# drv.net
KiCad netlist of a schematic drawn in Altium Designer
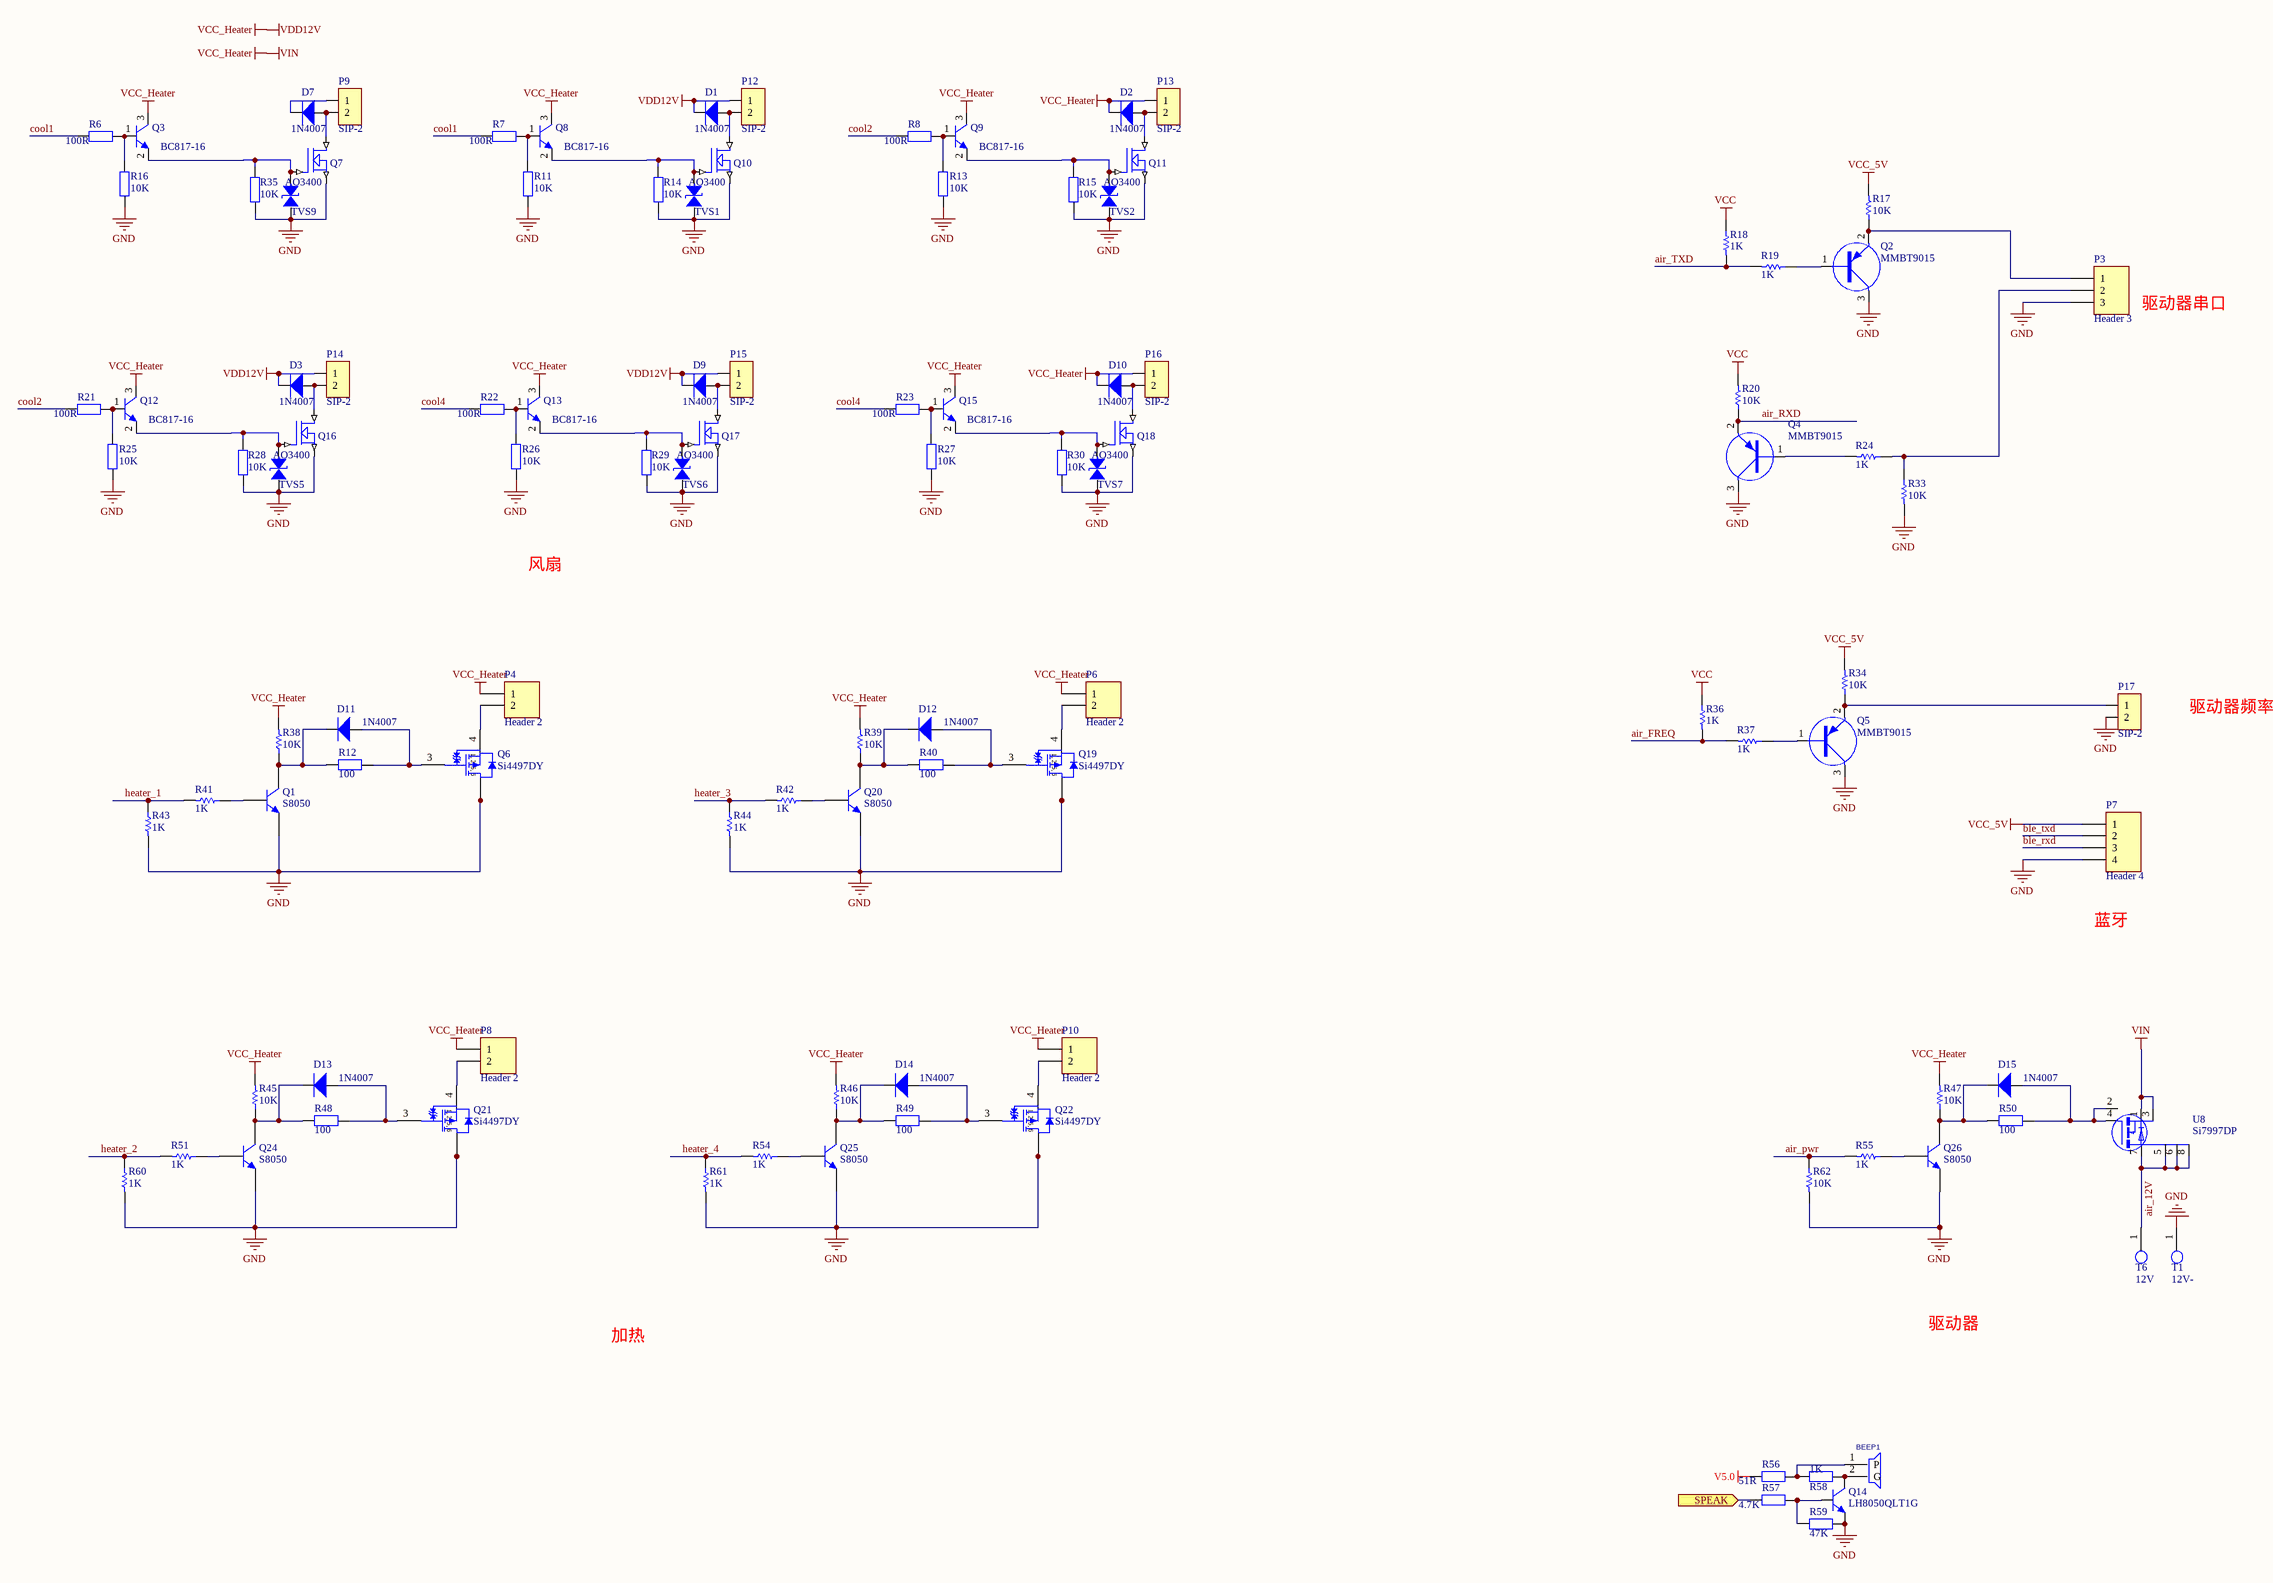
[diagram p0: drv.SchDoc]

(export (version "E")
  (design (tool "Eeschema 10.0.6"))
  (components
    (comp (ref "BEEP1")
      (value "BEEP-9.5X5.5")
      (footprint "BEEP-9.5X5.5")
      (libsource (lib "MINI-V3") (part "BEEP-9.5X5.5"))
    )
    (comp (ref "D1")
      (value "1N4007")
      (footprint "DO-214-AC")
      (description "贴片二极管")
      (libsource (lib "XiaoyI") (part "DIODE2"))
    )
    (comp (ref "D2")
      (value "1N4007")
      (footprint "DO-214-AC")
      (description "贴片二极管")
      (libsource (lib "XiaoyI") (part "DIODE2"))
    )
    (comp (ref "D3")
      (value "1N4007")
      (footprint "DO-214-AC")
      (description "贴片二极管")
      (libsource (lib "XiaoyI") (part "DIODE2"))
    )
    (comp (ref "D7")
      (value "1N4007")
      (footprint "DO-214-AC")
      (description "贴片二极管")
      (libsource (lib "XiaoyI") (part "DIODE2"))
    )
    (comp (ref "D9")
      (value "1N4007")
      (footprint "DO-214-AC")
      (description "贴片二极管")
      (libsource (lib "XiaoyI") (part "DIODE2"))
    )
    (comp (ref "D10")
      (value "1N4007")
      (footprint "DO-214-AC")
      (description "贴片二极管")
      (libsource (lib "XiaoyI") (part "DIODE2"))
    )
    (comp (ref "D11")
      (value "1N4007")
      (footprint "DO-214-AC")
      (description "贴片二极管")
      (libsource (lib "XiaoyI") (part "DIODE2"))
    )
    (comp (ref "D12")
      (value "1N4007")
      (footprint "DO-214-AC")
      (description "贴片二极管")
      (libsource (lib "XiaoyI") (part "DIODE2"))
    )
    (comp (ref "D13")
      (value "1N4007")
      (footprint "DO-214-AC")
      (description "贴片二极管")
      (libsource (lib "XiaoyI") (part "DIODE2"))
    )
    (comp (ref "D14")
      (value "1N4007")
      (footprint "DO-214-AC")
      (description "贴片二极管")
      (libsource (lib "XiaoyI") (part "DIODE2"))
    )
    (comp (ref "D15")
      (value "1N4007")
      (footprint "DO-214-AC")
      (description "贴片二极管")
      (libsource (lib "XiaoyI") (part "DIODE2"))
    )
    (comp (ref "P3")
      (value "Header 3")
      (footprint "HDR1X3")
      (description "Header, 3-Pin")
      (fields (field (name "PUBLISHER") "Altium Limited"))
      (libsource (lib "Miscellaneous Connectors") (part "Header 3"))
    )
    (comp (ref "P4")
      (value "Header 2")
      (footprint "HDR1X2")
      (description "Header, 2-Pin")
      (fields (field (name "PUBLISHER") "Altium Limited"))
      (libsource (lib "Miscellaneous Connectors") (part "Header 2"))
    )
    (comp (ref "P6")
      (value "Header 2")
      (footprint "HDR1X2")
      (description "Header, 2-Pin")
      (fields (field (name "PUBLISHER") "Altium Limited"))
      (libsource (lib "Miscellaneous Connectors") (part "Header 2"))
    )
    (comp (ref "P7")
      (value "Header 4")
      (footprint "HDR1X4")
      (description "Header, 4-Pin")
      (fields (field (name "PUBLISHER") "Altium Limited"))
      (libsource (lib "Miscellaneous Connectors") (part "Header 4"))
    )
    (comp (ref "P8")
      (value "Header 2")
      (footprint "HDR1X2")
      (description "Header, 2-Pin")
      (fields (field (name "PUBLISHER") "Altium Limited"))
      (libsource (lib "Miscellaneous Connectors") (part "Header 2"))
    )
    (comp (ref "P9")
      (value "SIP-2")
      (footprint "SIP-2A")
      (description "XH2.54 2P 立贴")
      (libsource (lib "XiaoyI") (part "SIP-2"))
    )
    (comp (ref "P10")
      (value "Header 2")
      (footprint "HDR1X2")
      (description "Header, 2-Pin")
      (fields (field (name "PUBLISHER") "Altium Limited"))
      (libsource (lib "Miscellaneous Connectors") (part "Header 2"))
    )
    (comp (ref "P12")
      (value "SIP-2")
      (footprint "SIP-2A")
      (description "XH2.54 2P 立贴")
      (libsource (lib "XiaoyI") (part "SIP-2"))
    )
    (comp (ref "P13")
      (value "SIP-2")
      (footprint "SIP-2A")
      (description "XH2.54 2P 立贴")
      (libsource (lib "XiaoyI") (part "SIP-2"))
    )
    (comp (ref "P14")
      (value "SIP-2")
      (footprint "SIP-2A")
      (description "XH2.54 2P 立贴")
      (libsource (lib "XiaoyI") (part "SIP-2"))
    )
    (comp (ref "P15")
      (value "SIP-2")
      (footprint "SIP-2A")
      (description "XH2.54 2P 立贴")
      (libsource (lib "XiaoyI") (part "SIP-2"))
    )
    (comp (ref "P16")
      (value "SIP-2")
      (footprint "SIP-2A")
      (description "XH2.54 2P 立贴")
      (libsource (lib "XiaoyI") (part "SIP-2"))
    )
    (comp (ref "P17")
      (value "SIP-2")
      (footprint "SIP-2A")
      (description "XH2.54 2P 立贴")
      (libsource (lib "XiaoyI") (part "SIP-2"))
    )
    (comp (ref "Q1")
      (value "S8050")
      (footprint "SOT23-3")
      (description "NPN Bipolar Transistor")
      (fields (field (name "PUBLISHER") "Altium Limited"))
      (libsource (lib "Miscellaneous Devices") (part "NPN"))
    )
    (comp (ref "Q2") (value "MMBT9015") (footprint "SOT23-3") (libsource (lib "Schlib1") (part "PNP")))
    (comp (ref "Q3")
      (value "BC817-16")
      (footprint "SOT-23")
      (description "三极管")
      (libsource (lib "XiaoyI") (part "NPN-1"))
    )
    (comp (ref "Q4") (value "MMBT9015") (footprint "SOT23-3") (libsource (lib "Schlib1") (part "PNP")))
    (comp (ref "Q5") (value "MMBT9015") (footprint "SOT23-3") (libsource (lib "Schlib1") (part "PNP")))
    (comp (ref "Q6")
      (value "Si4497DY")
      (description "Automotive P-Channel MOSFET, 6.9 A, 40 V, -55 to 175 degC, 6-Pin TSOP, RoHS, Tape and Reel")
      (fields (field (name "MANUFACTURER") "International Rectifier"))
      (libsource (lib "Bogen") (part "SQ3419AEEV-T1_GE3"))
    )
    (comp (ref "Q7")
      (value "AO3400")
      (footprint "SOT-23")
      (description "MOSFET N")
      (libsource (lib "XiaoyI") (part "MOSFET N"))
    )
    (comp (ref "Q8")
      (value "BC817-16")
      (footprint "SOT-23")
      (description "三极管")
      (libsource (lib "XiaoyI") (part "NPN-1"))
    )
    (comp (ref "Q9")
      (value "BC817-16")
      (footprint "SOT-23")
      (description "三极管")
      (libsource (lib "XiaoyI") (part "NPN-1"))
    )
    (comp (ref "Q10")
      (value "AO3400")
      (footprint "SOT-23")
      (description "MOSFET N")
      (libsource (lib "XiaoyI") (part "MOSFET N"))
    )
    (comp (ref "Q11")
      (value "AO3400")
      (footprint "SOT-23")
      (description "MOSFET N")
      (libsource (lib "XiaoyI") (part "MOSFET N"))
    )
    (comp (ref "Q12")
      (value "BC817-16")
      (footprint "SOT-23")
      (description "三极管")
      (libsource (lib "XiaoyI") (part "NPN-1"))
    )
    (comp (ref "Q13")
      (value "BC817-16")
      (footprint "SOT-23")
      (description "三极管")
      (libsource (lib "XiaoyI") (part "NPN-1"))
    )
    (comp (ref "Q14")
      (value "LH8050QLT1G")
      (footprint "SOT-23")
      (description "NPN")
      (libsource (lib "") (part "NPN-1_1"))
    )
    (comp (ref "Q15")
      (value "BC817-16")
      (footprint "SOT-23")
      (description "三极管")
      (libsource (lib "XiaoyI") (part "NPN-1"))
    )
    (comp (ref "Q16")
      (value "AO3400")
      (footprint "SOT-23")
      (description "MOSFET N")
      (libsource (lib "XiaoyI") (part "MOSFET N"))
    )
    (comp (ref "Q17")
      (value "AO3400")
      (footprint "SOT-23")
      (description "MOSFET N")
      (libsource (lib "XiaoyI") (part "MOSFET N"))
    )
    (comp (ref "Q18")
      (value "AO3400")
      (footprint "SOT-23")
      (description "MOSFET N")
      (libsource (lib "XiaoyI") (part "MOSFET N"))
    )
    (comp (ref "Q19")
      (value "Si4497DY")
      (description "Automotive P-Channel MOSFET, 6.9 A, 40 V, -55 to 175 degC, 6-Pin TSOP, RoHS, Tape and Reel")
      (fields (field (name "MANUFACTURER") "International Rectifier"))
      (libsource (lib "Bogen") (part "SQ3419AEEV-T1_GE3"))
    )
    (comp (ref "Q20")
      (value "S8050")
      (footprint "SOT23-3")
      (description "NPN Bipolar Transistor")
      (fields (field (name "PUBLISHER") "Altium Limited"))
      (libsource (lib "Miscellaneous Devices") (part "NPN"))
    )
    (comp (ref "Q21")
      (value "Si4497DY")
      (description "Automotive P-Channel MOSFET, 6.9 A, 40 V, -55 to 175 degC, 6-Pin TSOP, RoHS, Tape and Reel")
      (fields (field (name "MANUFACTURER") "International Rectifier"))
      (libsource (lib "Bogen") (part "SQ3419AEEV-T1_GE3"))
    )
    (comp (ref "Q22")
      (value "Si4497DY")
      (description "Automotive P-Channel MOSFET, 6.9 A, 40 V, -55 to 175 degC, 6-Pin TSOP, RoHS, Tape and Reel")
      (fields (field (name "MANUFACTURER") "International Rectifier"))
      (libsource (lib "Bogen") (part "SQ3419AEEV-T1_GE3"))
    )
    (comp (ref "Q24")
      (value "S8050")
      (footprint "SOT23-3")
      (description "NPN Bipolar Transistor")
      (fields (field (name "PUBLISHER") "Altium Limited"))
      (libsource (lib "Miscellaneous Devices") (part "NPN"))
    )
    (comp (ref "Q25")
      (value "S8050")
      (footprint "SOT23-3")
      (description "NPN Bipolar Transistor")
      (fields (field (name "PUBLISHER") "Altium Limited"))
      (libsource (lib "Miscellaneous Devices") (part "NPN"))
    )
    (comp (ref "Q26")
      (value "S8050")
      (footprint "SOT23-3")
      (description "NPN Bipolar Transistor")
      (fields (field (name "PUBLISHER") "Altium Limited"))
      (libsource (lib "Miscellaneous Devices") (part "NPN"))
    )
    (comp (ref "R6")
      (value "100R")
      (footprint "0603R")
      (description "贴片电阻 5%")
      (libsource (lib "") (part "RES-SOP_1"))
    )
    (comp (ref "R7")
      (value "100R")
      (footprint "0603R")
      (description "贴片电阻 5%")
      (libsource (lib "") (part "RES-SOP_1"))
    )
    (comp (ref "R8")
      (value "100R")
      (footprint "0603R")
      (description "贴片电阻 5%")
      (libsource (lib "") (part "RES-SOP_1"))
    )
    (comp (ref "R11")
      (value "10K")
      (footprint "0603R")
      (description "贴片电阻 5%")
      (libsource (lib "XiaoyI") (part "RES-SOP"))
    )
    (comp (ref "R12")
      (value "100")
      (footprint "0603R")
      (description "贴片电阻 5%")
      (libsource (lib "") (part "RES-SOP_2"))
    )
    (comp (ref "R13")
      (value "10K")
      (footprint "0603R")
      (description "贴片电阻 5%")
      (libsource (lib "XiaoyI") (part "RES-SOP"))
    )
    (comp (ref "R14")
      (value "10K")
      (footprint "0603R")
      (description "贴片电阻 5%")
      (libsource (lib "") (part "RES-SOP_3"))
    )
    (comp (ref "R15")
      (value "10K")
      (footprint "0603R")
      (description "贴片电阻 5%")
      (libsource (lib "") (part "RES-SOP_3"))
    )
    (comp (ref "R16")
      (value "10K")
      (footprint "0603R")
      (description "贴片电阻 5%")
      (libsource (lib "XiaoyI") (part "RES-SOP"))
    )
    (comp (ref "R17")
      (value "10K")
      (footprint "0603R")
      (description "Resistor")
      (fields (field (name "PUBLISHER") "Altium Limited"))
      (libsource (lib "Miscellaneous Devices") (part "Res1"))
    )
    (comp (ref "R18")
      (value "1K")
      (footprint "0603R")
      (description "Resistor")
      (fields (field (name "PUBLISHER") "Altium Limited"))
      (libsource (lib "Miscellaneous Devices") (part "Res1"))
    )
    (comp (ref "R19")
      (value "1K")
      (footprint "0603R")
      (description "Resistor")
      (fields (field (name "PUBLISHER") "Altium Limited"))
      (libsource (lib "Miscellaneous Devices") (part "Res1"))
    )
    (comp (ref "R20")
      (value "10K")
      (footprint "0603R")
      (description "Resistor")
      (fields (field (name "PUBLISHER") "Altium Limited"))
      (libsource (lib "Miscellaneous Devices") (part "Res1"))
    )
    (comp (ref "R21")
      (value "100R")
      (footprint "0603R")
      (description "贴片电阻 5%")
      (libsource (lib "") (part "RES-SOP_1"))
    )
    (comp (ref "R22")
      (value "100R")
      (footprint "0603R")
      (description "贴片电阻 5%")
      (libsource (lib "") (part "RES-SOP_1"))
    )
    (comp (ref "R23")
      (value "100R")
      (footprint "0603R")
      (description "贴片电阻 5%")
      (libsource (lib "") (part "RES-SOP_1"))
    )
    (comp (ref "R24")
      (value "1K")
      (footprint "0603R")
      (description "Resistor")
      (fields (field (name "PUBLISHER") "Altium Limited"))
      (libsource (lib "Miscellaneous Devices") (part "Res1"))
    )
    (comp (ref "R25")
      (value "10K")
      (footprint "0603R")
      (description "贴片电阻 5%")
      (libsource (lib "XiaoyI") (part "RES-SOP"))
    )
    (comp (ref "R26")
      (value "10K")
      (footprint "0603R")
      (description "贴片电阻 5%")
      (libsource (lib "XiaoyI") (part "RES-SOP"))
    )
    (comp (ref "R27")
      (value "10K")
      (footprint "0603R")
      (description "贴片电阻 5%")
      (libsource (lib "XiaoyI") (part "RES-SOP"))
    )
    (comp (ref "R28")
      (value "10K")
      (footprint "0603R")
      (description "贴片电阻 5%")
      (libsource (lib "") (part "RES-SOP_3"))
    )
    (comp (ref "R29")
      (value "10K")
      (footprint "0603R")
      (description "贴片电阻 5%")
      (libsource (lib "") (part "RES-SOP_3"))
    )
    (comp (ref "R30")
      (value "10K")
      (footprint "0603R")
      (description "贴片电阻 5%")
      (libsource (lib "") (part "RES-SOP_3"))
    )
    (comp (ref "R33")
      (value "10K")
      (footprint "0603R")
      (description "Resistor")
      (fields (field (name "PUBLISHER") "Altium Limited"))
      (libsource (lib "Miscellaneous Devices") (part "Res1"))
    )
    (comp (ref "R34")
      (value "10K")
      (footprint "0603R")
      (description "Resistor")
      (fields (field (name "PUBLISHER") "Altium Limited"))
      (libsource (lib "Miscellaneous Devices") (part "Res1"))
    )
    (comp (ref "R35")
      (value "10K")
      (footprint "0603R")
      (description "贴片电阻 5%")
      (libsource (lib "") (part "RES-SOP_3"))
    )
    (comp (ref "R36")
      (value "1K")
      (footprint "0603R")
      (description "Resistor")
      (fields (field (name "PUBLISHER") "Altium Limited"))
      (libsource (lib "Miscellaneous Devices") (part "Res1"))
    )
    (comp (ref "R37")
      (value "1K")
      (footprint "0603R")
      (description "Resistor")
      (fields (field (name "PUBLISHER") "Altium Limited"))
      (libsource (lib "Miscellaneous Devices") (part "Res1"))
    )
    (comp (ref "R38")
      (value "10K")
      (footprint "0603R")
      (description "Resistor")
      (fields (field (name "PUBLISHER") "Altium Limited"))
      (libsource (lib "Miscellaneous Devices") (part "Res1"))
    )
    (comp (ref "R39")
      (value "10K")
      (footprint "0603R")
      (description "Resistor")
      (fields (field (name "PUBLISHER") "Altium Limited"))
      (libsource (lib "Miscellaneous Devices") (part "Res1"))
    )
    (comp (ref "R40")
      (value "100")
      (footprint "0603R")
      (description "贴片电阻 5%")
      (libsource (lib "") (part "RES-SOP_2"))
    )
    (comp (ref "R41")
      (value "1K")
      (footprint "0603R")
      (description "Resistor")
      (fields (field (name "PUBLISHER") "Altium Limited"))
      (libsource (lib "Miscellaneous Devices") (part "Res1"))
    )
    (comp (ref "R42")
      (value "1K")
      (footprint "0603R")
      (description "Resistor")
      (fields (field (name "PUBLISHER") "Altium Limited"))
      (libsource (lib "Miscellaneous Devices") (part "Res1"))
    )
    (comp (ref "R43")
      (value "1K")
      (footprint "0603R")
      (description "Resistor")
      (fields (field (name "PUBLISHER") "Altium Limited"))
      (libsource (lib "Miscellaneous Devices") (part "Res1"))
    )
    (comp (ref "R44")
      (value "1K")
      (footprint "0603R")
      (description "Resistor")
      (fields (field (name "PUBLISHER") "Altium Limited"))
      (libsource (lib "Miscellaneous Devices") (part "Res1"))
    )
    (comp (ref "R45")
      (value "10K")
      (footprint "0603R")
      (description "Resistor")
      (fields (field (name "PUBLISHER") "Altium Limited"))
      (libsource (lib "Miscellaneous Devices") (part "Res1"))
    )
    (comp (ref "R46")
      (value "10K")
      (footprint "0603R")
      (description "Resistor")
      (fields (field (name "PUBLISHER") "Altium Limited"))
      (libsource (lib "Miscellaneous Devices") (part "Res1"))
    )
    (comp (ref "R47")
      (value "10K")
      (footprint "0603R")
      (description "Resistor")
      (fields (field (name "PUBLISHER") "Altium Limited"))
      (libsource (lib "Miscellaneous Devices") (part "Res1"))
    )
    (comp (ref "R48")
      (value "100")
      (footprint "0603R")
      (description "贴片电阻 5%")
      (libsource (lib "") (part "RES-SOP_2"))
    )
    (comp (ref "R49")
      (value "100")
      (footprint "0603R")
      (description "贴片电阻 5%")
      (libsource (lib "") (part "RES-SOP_2"))
    )
    (comp (ref "R50")
      (value "100")
      (footprint "0603R")
      (description "贴片电阻 5%")
      (libsource (lib "") (part "RES-SOP_2"))
    )
    (comp (ref "R51")
      (value "1K")
      (footprint "0603R")
      (description "Resistor")
      (fields (field (name "PUBLISHER") "Altium Limited"))
      (libsource (lib "Miscellaneous Devices") (part "Res1"))
    )
    (comp (ref "R54")
      (value "1K")
      (footprint "0603R")
      (description "Resistor")
      (fields (field (name "PUBLISHER") "Altium Limited"))
      (libsource (lib "Miscellaneous Devices") (part "Res1"))
    )
    (comp (ref "R55")
      (value "1K")
      (footprint "0603R")
      (description "Resistor")
      (fields (field (name "PUBLISHER") "Altium Limited"))
      (libsource (lib "Miscellaneous Devices") (part "Res1"))
    )
    (comp (ref "R56")
      (value "51R")
      (footprint "0603R")
      (description "贴片电阻 5%")
      (libsource (lib "ABB") (part "RES0"))
    )
    (comp (ref "R57")
      (value "4.7K")
      (footprint "0603R")
      (description "贴片电阻 5%")
      (libsource (lib "") (part "RES0_1"))
    )
    (comp (ref "R58")
      (value "1K")
      (footprint "0603R")
      (description "贴片电阻 5%")
      (libsource (lib "ABB") (part "RES0"))
    )
    (comp (ref "R59")
      (value "47K")
      (footprint "0603R")
      (description "贴片电阻 5%")
      (libsource (lib "") (part "RES0_1"))
    )
    (comp (ref "R60")
      (value "1K")
      (footprint "0603R")
      (description "Resistor")
      (fields (field (name "PUBLISHER") "Altium Limited"))
      (libsource (lib "Miscellaneous Devices") (part "Res1"))
    )
    (comp (ref "R61")
      (value "1K")
      (footprint "0603R")
      (description "Resistor")
      (fields (field (name "PUBLISHER") "Altium Limited"))
      (libsource (lib "Miscellaneous Devices") (part "Res1"))
    )
    (comp (ref "R62")
      (value "10K")
      (footprint "0603R")
      (description "Resistor")
      (fields (field (name "PUBLISHER") "Altium Limited"))
      (libsource (lib "Miscellaneous Devices") (part "Res1"))
    )
    (comp (ref "T1") (value "12V-") (footprint "FIX-4.5") (libsource (lib "Schlib_20110825") (part "TP")))
    (comp (ref "T6") (value "12V") (footprint "FIX-4.5") (libsource (lib "Schlib_20110825") (part "TP")))
    (comp (ref "TVS1")
      (value "ESD5Z5.0CT1G")
      (footprint "SOD-523")
      (description "TVS")
      (libsource (lib "XiaoyI") (part "TVS-1"))
    )
    (comp (ref "TVS2")
      (value "ESD5Z5.0CT1G")
      (footprint "SOD-523")
      (description "TVS")
      (libsource (lib "XiaoyI") (part "TVS-1"))
    )
    (comp (ref "TVS5")
      (value "ESD5Z5.0CT1G")
      (footprint "SOD-523")
      (description "TVS")
      (libsource (lib "XiaoyI") (part "TVS-1"))
    )
    (comp (ref "TVS6")
      (value "ESD5Z5.0CT1G")
      (footprint "SOD-523")
      (description "TVS")
      (libsource (lib "XiaoyI") (part "TVS-1"))
    )
    (comp (ref "TVS7")
      (value "ESD5Z5.0CT1G")
      (footprint "SOD-523")
      (description "TVS")
      (libsource (lib "XiaoyI") (part "TVS-1"))
    )
    (comp (ref "TVS9")
      (value "ESD5Z5.0CT1G")
      (footprint "SOD-523")
      (description "TVS")
      (libsource (lib "XiaoyI") (part "TVS-1"))
    )
    (comp (ref "U8")
      (value "Si7997DP")
      (footprint "SC-70(PowerPAK)")
      (description "Sia430DJ")
      (libsource (lib "Schlib_20110825") (part "Si7997DP"))
    )
  )
  (nets
    (net (code "1") (name "/SPEAK") (class "Default")
      (node (ref "R57") (pin "1") (pinfunction "1_1") (pintype "passive"))
    )
    (net (code "2") (name "/air_12V") (class "Default")
      (node (ref "T6") (pin "1") (pintype "passive"))
      (node (ref "U8") (pin "5") (pinfunction "D_5") (pintype "passive"))
      (node (ref "U8") (pin "6") (pinfunction "D_6") (pintype "passive"))
      (node (ref "U8") (pin "7") (pinfunction "D_7") (pintype "passive"))
      (node (ref "U8") (pin "8") (pinfunction "D_8") (pintype "passive"))
    )
    (net (code "3") (name "/air_FREQ") (class "Default")
      (node (ref "R36") (pin "2") (pinfunction "2_2") (pintype "passive"))
      (node (ref "R37") (pin "2") (pinfunction "2_2") (pintype "passive"))
    )
    (net (code "4") (name "/air_RXD") (class "Default")
      (node (ref "Q4") (pin "2") (pinfunction "E_2") (pintype "passive"))
      (node (ref "R20") (pin "1") (pinfunction "1_1") (pintype "passive"))
    )
    (net (code "5") (name "/air_TXD") (class "Default")
      (node (ref "R18") (pin "2") (pinfunction "2_2") (pintype "passive"))
      (node (ref "R19") (pin "2") (pinfunction "2_2") (pintype "passive"))
    )
    (net (code "6") (name "/air_pwr") (class "Default")
      (node (ref "R55") (pin "2") (pinfunction "2_2") (pintype "passive"))
      (node (ref "R62") (pin "1") (pinfunction "1_1") (pintype "passive"))
    )
    (net (code "7") (name "/ble_rxd") (class "Default")
      (node (ref "P7") (pin "3") (pinfunction "3_3") (pintype "passive"))
    )
    (net (code "8") (name "/ble_txd") (class "Default")
      (node (ref "P7") (pin "2") (pinfunction "2_2") (pintype "passive"))
    )
    (net (code "9") (name "/cool1") (class "Default")
      (node (ref "R6") (pin "2") (pinfunction "2_2") (pintype "passive"))
      (node (ref "R7") (pin "2") (pinfunction "2_2") (pintype "passive"))
    )
    (net (code "10") (name "/cool2") (class "Default")
      (node (ref "R21") (pin "2") (pinfunction "2_2") (pintype "passive"))
      (node (ref "R8") (pin "2") (pinfunction "2_2") (pintype "passive"))
    )
    (net (code "11") (name "/cool4") (class "Default")
      (node (ref "R22") (pin "2") (pinfunction "2_2") (pintype "passive"))
      (node (ref "R23") (pin "2") (pinfunction "2_2") (pintype "passive"))
    )
    (net (code "12") (name "/heater_1") (class "Default")
      (node (ref "R41") (pin "2") (pinfunction "2_2") (pintype "passive"))
      (node (ref "R43") (pin "1") (pinfunction "1_1") (pintype "passive"))
    )
    (net (code "13") (name "/heater_2") (class "Default")
      (node (ref "R51") (pin "2") (pinfunction "2_2") (pintype "passive"))
      (node (ref "R60") (pin "1") (pinfunction "1_1") (pintype "passive"))
    )
    (net (code "14") (name "/heater_3") (class "Default")
      (node (ref "R42") (pin "2") (pinfunction "2_2") (pintype "passive"))
      (node (ref "R44") (pin "1") (pinfunction "1_1") (pintype "passive"))
    )
    (net (code "15") (name "/heater_4") (class "Default")
      (node (ref "R54") (pin "2") (pinfunction "2_2") (pintype "passive"))
      (node (ref "R61") (pin "1") (pinfunction "1_1") (pintype "passive"))
    )
    (net (code "16") (name "GND") (class "Default")
      (node (ref "P17") (pin "2") (pinfunction "2_2") (pintype "passive"))
      (node (ref "P3") (pin "3") (pinfunction "3_3") (pintype "passive"))
      (node (ref "P7") (pin "4") (pinfunction "4_4") (pintype "passive"))
      (node (ref "Q1") (pin "2") (pinfunction "E_2") (pintype "passive"))
      (node (ref "Q10") (pin "2") (pinfunction "S_2") (pintype "output"))
      (node (ref "Q11") (pin "2") (pinfunction "S_2") (pintype "output"))
      (node (ref "Q14") (pin "2") (pinfunction "E_2") (pintype "passive"))
      (node (ref "Q16") (pin "2") (pinfunction "S_2") (pintype "output"))
      (node (ref "Q17") (pin "2") (pinfunction "S_2") (pintype "output"))
      (node (ref "Q18") (pin "2") (pinfunction "S_2") (pintype "output"))
      (node (ref "Q19") (pin "1") (pinfunction "D_1") (pintype "passive"))
      (node (ref "Q19") (pin "2") (pinfunction "D_2") (pintype "passive"))
      (node (ref "Q19") (pin "5") (pinfunction "D_5") (pintype "passive"))
      (node (ref "Q19") (pin "6") (pinfunction "D_6") (pintype "passive"))
      (node (ref "Q2") (pin "3") (pinfunction "C_3") (pintype "passive"))
      (node (ref "Q20") (pin "2") (pinfunction "E_2") (pintype "passive"))
      (node (ref "Q21") (pin "1") (pinfunction "D_1") (pintype "passive"))
      (node (ref "Q21") (pin "2") (pinfunction "D_2") (pintype "passive"))
      (node (ref "Q21") (pin "5") (pinfunction "D_5") (pintype "passive"))
      (node (ref "Q21") (pin "6") (pinfunction "D_6") (pintype "passive"))
      (node (ref "Q22") (pin "1") (pinfunction "D_1") (pintype "passive"))
      (node (ref "Q22") (pin "2") (pinfunction "D_2") (pintype "passive"))
      (node (ref "Q22") (pin "5") (pinfunction "D_5") (pintype "passive"))
      (node (ref "Q22") (pin "6") (pinfunction "D_6") (pintype "passive"))
      (node (ref "Q24") (pin "2") (pinfunction "E_2") (pintype "passive"))
      (node (ref "Q25") (pin "2") (pinfunction "E_2") (pintype "passive"))
      (node (ref "Q26") (pin "2") (pinfunction "E_2") (pintype "passive"))
      (node (ref "Q4") (pin "3") (pinfunction "C_3") (pintype "passive"))
      (node (ref "Q5") (pin "3") (pinfunction "C_3") (pintype "passive"))
      (node (ref "Q6") (pin "1") (pinfunction "D_1") (pintype "passive"))
      (node (ref "Q6") (pin "2") (pinfunction "D_2") (pintype "passive"))
      (node (ref "Q6") (pin "5") (pinfunction "D_5") (pintype "passive"))
      (node (ref "Q6") (pin "6") (pinfunction "D_6") (pintype "passive"))
      (node (ref "Q7") (pin "2") (pinfunction "S_2") (pintype "output"))
      (node (ref "R11") (pin "1") (pinfunction "1_1") (pintype "passive"))
      (node (ref "R13") (pin "1") (pinfunction "1_1") (pintype "passive"))
      (node (ref "R14") (pin "2") (pinfunction "2_2") (pintype "passive"))
      (node (ref "R15") (pin "2") (pinfunction "2_2") (pintype "passive"))
      (node (ref "R16") (pin "1") (pinfunction "1_1") (pintype "passive"))
      (node (ref "R25") (pin "1") (pinfunction "1_1") (pintype "passive"))
      (node (ref "R26") (pin "1") (pinfunction "1_1") (pintype "passive"))
      (node (ref "R27") (pin "1") (pinfunction "1_1") (pintype "passive"))
      (node (ref "R28") (pin "2") (pinfunction "2_2") (pintype "passive"))
      (node (ref "R29") (pin "2") (pinfunction "2_2") (pintype "passive"))
      (node (ref "R30") (pin "2") (pinfunction "2_2") (pintype "passive"))
      (node (ref "R33") (pin "2") (pinfunction "2_2") (pintype "passive"))
      (node (ref "R35") (pin "2") (pinfunction "2_2") (pintype "passive"))
      (node (ref "R43") (pin "2") (pinfunction "2_2") (pintype "passive"))
      (node (ref "R44") (pin "2") (pinfunction "2_2") (pintype "passive"))
      (node (ref "R59") (pin "2") (pinfunction "2_2") (pintype "passive"))
      (node (ref "R60") (pin "2") (pinfunction "2_2") (pintype "passive"))
      (node (ref "R61") (pin "2") (pinfunction "2_2") (pintype "passive"))
      (node (ref "R62") (pin "2") (pinfunction "2_2") (pintype "passive"))
      (node (ref "T1") (pin "1") (pintype "passive"))
      (node (ref "TVS1") (pin "1") (pinfunction "A_1") (pintype "passive"))
      (node (ref "TVS2") (pin "1") (pinfunction "A_1") (pintype "passive"))
      (node (ref "TVS5") (pin "1") (pinfunction "A_1") (pintype "passive"))
      (node (ref "TVS6") (pin "1") (pinfunction "A_1") (pintype "passive"))
      (node (ref "TVS7") (pin "1") (pinfunction "A_1") (pintype "passive"))
      (node (ref "TVS9") (pin "1") (pinfunction "A_1") (pintype "passive"))
    )
    (net (code "17") (name "Net-(BEEP1-G)") (class "Default")
      (node (ref "BEEP1") (pin "2") (pinfunction "G_2") (pintype "passive"))
      (node (ref "Q14") (pin "3") (pinfunction "C_3") (pintype "passive"))
      (node (ref "R58") (pin "1") (pinfunction "1_1") (pintype "passive"))
    )
    (net (code "18") (name "Net-(BEEP1-P)") (class "Default")
      (node (ref "BEEP1") (pin "1") (pinfunction "P_1") (pintype "passive"))
      (node (ref "R56") (pin "1") (pinfunction "1_1") (pintype "passive"))
      (node (ref "R58") (pin "2") (pinfunction "2_2") (pintype "passive"))
    )
    (net (code "19") (name "Net-(D1-A)") (class "Default")
      (node (ref "D1") (pin "1") (pinfunction "A_1") (pintype "passive"))
      (node (ref "P12") (pin "2") (pinfunction "2_2") (pintype "passive"))
      (node (ref "Q10") (pin "3") (pinfunction "D_3") (pintype "input"))
    )
    (net (code "20") (name "Net-(D2-A)") (class "Default")
      (node (ref "D2") (pin "1") (pinfunction "A_1") (pintype "passive"))
      (node (ref "P13") (pin "2") (pinfunction "2_2") (pintype "passive"))
      (node (ref "Q11") (pin "3") (pinfunction "D_3") (pintype "input"))
    )
    (net (code "21") (name "Net-(D3-A)") (class "Default")
      (node (ref "D3") (pin "1") (pinfunction "A_1") (pintype "passive"))
      (node (ref "P14") (pin "2") (pinfunction "2_2") (pintype "passive"))
      (node (ref "Q16") (pin "3") (pinfunction "D_3") (pintype "input"))
    )
    (net (code "22") (name "Net-(D7-A)") (class "Default")
      (node (ref "D7") (pin "1") (pinfunction "A_1") (pintype "passive"))
      (node (ref "P9") (pin "2") (pinfunction "2_2") (pintype "passive"))
      (node (ref "Q7") (pin "3") (pinfunction "D_3") (pintype "input"))
    )
    (net (code "23") (name "Net-(D7-K)") (class "Default")
      (node (ref "D7") (pin "2") (pinfunction "K_2") (pintype "passive"))
      (node (ref "P9") (pin "1") (pinfunction "1_1") (pintype "passive"))
    )
    (net (code "24") (name "Net-(D9-A)") (class "Default")
      (node (ref "D9") (pin "1") (pinfunction "A_1") (pintype "passive"))
      (node (ref "P15") (pin "2") (pinfunction "2_2") (pintype "passive"))
      (node (ref "Q17") (pin "3") (pinfunction "D_3") (pintype "input"))
    )
    (net (code "25") (name "Net-(D10-A)") (class "Default")
      (node (ref "D10") (pin "1") (pinfunction "A_1") (pintype "passive"))
      (node (ref "P16") (pin "2") (pinfunction "2_2") (pintype "passive"))
      (node (ref "Q18") (pin "3") (pinfunction "D_3") (pintype "input"))
    )
    (net (code "26") (name "Net-(D11-A)") (class "Default")
      (node (ref "D11") (pin "1") (pinfunction "A_1") (pintype "passive"))
      (node (ref "Q6") (pin "3") (pinfunction "G_3") (pintype "passive"))
      (node (ref "R12") (pin "2") (pinfunction "2_2") (pintype "passive"))
    )
    (net (code "27") (name "Net-(D11-K)") (class "Default")
      (node (ref "D11") (pin "2") (pinfunction "K_2") (pintype "passive"))
      (node (ref "Q1") (pin "3") (pinfunction "C_3") (pintype "passive"))
      (node (ref "R12") (pin "1") (pinfunction "1_1") (pintype "passive"))
      (node (ref "R38") (pin "1") (pinfunction "1_1") (pintype "passive"))
    )
    (net (code "28") (name "Net-(D12-A)") (class "Default")
      (node (ref "D12") (pin "1") (pinfunction "A_1") (pintype "passive"))
      (node (ref "Q19") (pin "3") (pinfunction "G_3") (pintype "passive"))
      (node (ref "R40") (pin "2") (pinfunction "2_2") (pintype "passive"))
    )
    (net (code "29") (name "Net-(D12-K)") (class "Default")
      (node (ref "D12") (pin "2") (pinfunction "K_2") (pintype "passive"))
      (node (ref "Q20") (pin "3") (pinfunction "C_3") (pintype "passive"))
      (node (ref "R39") (pin "1") (pinfunction "1_1") (pintype "passive"))
      (node (ref "R40") (pin "1") (pinfunction "1_1") (pintype "passive"))
    )
    (net (code "30") (name "Net-(D13-A)") (class "Default")
      (node (ref "D13") (pin "1") (pinfunction "A_1") (pintype "passive"))
      (node (ref "Q21") (pin "3") (pinfunction "G_3") (pintype "passive"))
      (node (ref "R48") (pin "2") (pinfunction "2_2") (pintype "passive"))
    )
    (net (code "31") (name "Net-(D13-K)") (class "Default")
      (node (ref "D13") (pin "2") (pinfunction "K_2") (pintype "passive"))
      (node (ref "Q24") (pin "3") (pinfunction "C_3") (pintype "passive"))
      (node (ref "R45") (pin "1") (pinfunction "1_1") (pintype "passive"))
      (node (ref "R48") (pin "1") (pinfunction "1_1") (pintype "passive"))
    )
    (net (code "32") (name "Net-(D14-A)") (class "Default")
      (node (ref "D14") (pin "1") (pinfunction "A_1") (pintype "passive"))
      (node (ref "Q22") (pin "3") (pinfunction "G_3") (pintype "passive"))
      (node (ref "R49") (pin "2") (pinfunction "2_2") (pintype "passive"))
    )
    (net (code "33") (name "Net-(D14-K)") (class "Default")
      (node (ref "D14") (pin "2") (pinfunction "K_2") (pintype "passive"))
      (node (ref "Q25") (pin "3") (pinfunction "C_3") (pintype "passive"))
      (node (ref "R46") (pin "1") (pinfunction "1_1") (pintype "passive"))
      (node (ref "R49") (pin "1") (pinfunction "1_1") (pintype "passive"))
    )
    (net (code "34") (name "Net-(D15-A)") (class "Default")
      (node (ref "D15") (pin "1") (pinfunction "A_1") (pintype "passive"))
      (node (ref "R50") (pin "2") (pinfunction "2_2") (pintype "passive"))
      (node (ref "U8") (pin "2") (pinfunction "G_2") (pintype "passive"))
      (node (ref "U8") (pin "4") (pinfunction "G_4") (pintype "passive"))
    )
    (net (code "35") (name "Net-(D15-K)") (class "Default")
      (node (ref "D15") (pin "2") (pinfunction "K_2") (pintype "passive"))
      (node (ref "Q26") (pin "3") (pinfunction "C_3") (pintype "passive"))
      (node (ref "R47") (pin "1") (pinfunction "1_1") (pintype "passive"))
      (node (ref "R50") (pin "1") (pinfunction "1_1") (pintype "passive"))
    )
    (net (code "36") (name "Net-(P3-Pad2)") (class "Default")
      (node (ref "P3") (pin "2") (pinfunction "2_2") (pintype "passive"))
      (node (ref "R24") (pin "1") (pinfunction "1_1") (pintype "passive"))
      (node (ref "R33") (pin "1") (pinfunction "1_1") (pintype "passive"))
    )
    (net (code "37") (name "Net-(Q1-B)") (class "Default")
      (node (ref "Q1") (pin "1") (pinfunction "B_1") (pintype "passive"))
      (node (ref "R41") (pin "1") (pinfunction "1_1") (pintype "passive"))
    )
    (net (code "38") (name "Net-(Q2-B)") (class "Default")
      (node (ref "Q2") (pin "1") (pinfunction "B_1") (pintype "passive"))
      (node (ref "R19") (pin "1") (pinfunction "1_1") (pintype "passive"))
    )
    (net (code "39") (name "Net-(Q2-E)") (class "Default")
      (node (ref "P3") (pin "1") (pinfunction "1_1") (pintype "passive"))
      (node (ref "Q2") (pin "2") (pinfunction "E_2") (pintype "passive"))
      (node (ref "R17") (pin "1") (pinfunction "1_1") (pintype "passive"))
    )
    (net (code "40") (name "Net-(Q3-B)") (class "Default")
      (node (ref "Q3") (pin "1") (pinfunction "B_1") (pintype "passive"))
      (node (ref "R16") (pin "2") (pinfunction "2_2") (pintype "passive"))
      (node (ref "R6") (pin "1") (pinfunction "1_1") (pintype "passive"))
    )
    (net (code "41") (name "Net-(Q3-E)") (class "Default")
      (node (ref "Q3") (pin "2") (pinfunction "E_2") (pintype "passive"))
      (node (ref "Q7") (pin "1") (pinfunction "G_1") (pintype "input"))
      (node (ref "R35") (pin "1") (pinfunction "1_1") (pintype "passive"))
      (node (ref "TVS9") (pin "2") (pinfunction "B_2") (pintype "passive"))
    )
    (net (code "42") (name "Net-(Q4-B)") (class "Default")
      (node (ref "Q4") (pin "1") (pinfunction "B_1") (pintype "passive"))
      (node (ref "R24") (pin "2") (pinfunction "2_2") (pintype "passive"))
    )
    (net (code "43") (name "Net-(Q5-B)") (class "Default")
      (node (ref "Q5") (pin "1") (pinfunction "B_1") (pintype "passive"))
      (node (ref "R37") (pin "1") (pinfunction "1_1") (pintype "passive"))
    )
    (net (code "44") (name "Net-(Q5-E)") (class "Default")
      (node (ref "P17") (pin "1") (pinfunction "1_1") (pintype "passive"))
      (node (ref "Q5") (pin "2") (pinfunction "E_2") (pintype "passive"))
      (node (ref "R34") (pin "1") (pinfunction "1_1") (pintype "passive"))
    )
    (net (code "45") (name "Net-(Q6-S)") (class "Default")
      (node (ref "P4") (pin "2") (pinfunction "2_2") (pintype "passive"))
      (node (ref "Q6") (pin "4") (pinfunction "S_4") (pintype "passive"))
    )
    (net (code "46") (name "Net-(Q8-B)") (class "Default")
      (node (ref "Q8") (pin "1") (pinfunction "B_1") (pintype "passive"))
      (node (ref "R11") (pin "2") (pinfunction "2_2") (pintype "passive"))
      (node (ref "R7") (pin "1") (pinfunction "1_1") (pintype "passive"))
    )
    (net (code "47") (name "Net-(Q9-B)") (class "Default")
      (node (ref "Q9") (pin "1") (pinfunction "B_1") (pintype "passive"))
      (node (ref "R13") (pin "2") (pinfunction "2_2") (pintype "passive"))
      (node (ref "R8") (pin "1") (pinfunction "1_1") (pintype "passive"))
    )
    (net (code "48") (name "Net-(Q10-G)") (class "Default")
      (node (ref "Q10") (pin "1") (pinfunction "G_1") (pintype "input"))
      (node (ref "Q8") (pin "2") (pinfunction "E_2") (pintype "passive"))
      (node (ref "R14") (pin "1") (pinfunction "1_1") (pintype "passive"))
      (node (ref "TVS1") (pin "2") (pinfunction "B_2") (pintype "passive"))
    )
    (net (code "49") (name "Net-(Q11-G)") (class "Default")
      (node (ref "Q11") (pin "1") (pinfunction "G_1") (pintype "input"))
      (node (ref "Q9") (pin "2") (pinfunction "E_2") (pintype "passive"))
      (node (ref "R15") (pin "1") (pinfunction "1_1") (pintype "passive"))
      (node (ref "TVS2") (pin "2") (pinfunction "B_2") (pintype "passive"))
    )
    (net (code "50") (name "Net-(Q12-B)") (class "Default")
      (node (ref "Q12") (pin "1") (pinfunction "B_1") (pintype "passive"))
      (node (ref "R21") (pin "1") (pinfunction "1_1") (pintype "passive"))
      (node (ref "R25") (pin "2") (pinfunction "2_2") (pintype "passive"))
    )
    (net (code "51") (name "Net-(Q12-E)") (class "Default")
      (node (ref "Q12") (pin "2") (pinfunction "E_2") (pintype "passive"))
      (node (ref "Q16") (pin "1") (pinfunction "G_1") (pintype "input"))
      (node (ref "R28") (pin "1") (pinfunction "1_1") (pintype "passive"))
      (node (ref "TVS5") (pin "2") (pinfunction "B_2") (pintype "passive"))
    )
    (net (code "52") (name "Net-(Q13-B)") (class "Default")
      (node (ref "Q13") (pin "1") (pinfunction "B_1") (pintype "passive"))
      (node (ref "R22") (pin "1") (pinfunction "1_1") (pintype "passive"))
      (node (ref "R26") (pin "2") (pinfunction "2_2") (pintype "passive"))
    )
    (net (code "53") (name "Net-(Q13-E)") (class "Default")
      (node (ref "Q13") (pin "2") (pinfunction "E_2") (pintype "passive"))
      (node (ref "Q17") (pin "1") (pinfunction "G_1") (pintype "input"))
      (node (ref "R29") (pin "1") (pinfunction "1_1") (pintype "passive"))
      (node (ref "TVS6") (pin "2") (pinfunction "B_2") (pintype "passive"))
    )
    (net (code "54") (name "Net-(Q14-B)") (class "Default")
      (node (ref "Q14") (pin "1") (pinfunction "B_1") (pintype "passive"))
      (node (ref "R57") (pin "2") (pinfunction "2_2") (pintype "passive"))
      (node (ref "R59") (pin "1") (pinfunction "1_1") (pintype "passive"))
    )
    (net (code "55") (name "Net-(Q15-B)") (class "Default")
      (node (ref "Q15") (pin "1") (pinfunction "B_1") (pintype "passive"))
      (node (ref "R23") (pin "1") (pinfunction "1_1") (pintype "passive"))
      (node (ref "R27") (pin "2") (pinfunction "2_2") (pintype "passive"))
    )
    (net (code "56") (name "Net-(Q15-E)") (class "Default")
      (node (ref "Q15") (pin "2") (pinfunction "E_2") (pintype "passive"))
      (node (ref "Q18") (pin "1") (pinfunction "G_1") (pintype "input"))
      (node (ref "R30") (pin "1") (pinfunction "1_1") (pintype "passive"))
      (node (ref "TVS7") (pin "2") (pinfunction "B_2") (pintype "passive"))
    )
    (net (code "57") (name "Net-(Q19-S)") (class "Default")
      (node (ref "P6") (pin "2") (pinfunction "2_2") (pintype "passive"))
      (node (ref "Q19") (pin "4") (pinfunction "S_4") (pintype "passive"))
    )
    (net (code "58") (name "Net-(Q20-B)") (class "Default")
      (node (ref "Q20") (pin "1") (pinfunction "B_1") (pintype "passive"))
      (node (ref "R42") (pin "1") (pinfunction "1_1") (pintype "passive"))
    )
    (net (code "59") (name "Net-(Q21-S)") (class "Default")
      (node (ref "P8") (pin "2") (pinfunction "2_2") (pintype "passive"))
      (node (ref "Q21") (pin "4") (pinfunction "S_4") (pintype "passive"))
    )
    (net (code "60") (name "Net-(Q22-S)") (class "Default")
      (node (ref "P10") (pin "2") (pinfunction "2_2") (pintype "passive"))
      (node (ref "Q22") (pin "4") (pinfunction "S_4") (pintype "passive"))
    )
    (net (code "61") (name "Net-(Q24-B)") (class "Default")
      (node (ref "Q24") (pin "1") (pinfunction "B_1") (pintype "passive"))
      (node (ref "R51") (pin "1") (pinfunction "1_1") (pintype "passive"))
    )
    (net (code "62") (name "Net-(Q25-B)") (class "Default")
      (node (ref "Q25") (pin "1") (pinfunction "B_1") (pintype "passive"))
      (node (ref "R54") (pin "1") (pinfunction "1_1") (pintype "passive"))
    )
    (net (code "63") (name "Net-(Q26-B)") (class "Default")
      (node (ref "Q26") (pin "1") (pinfunction "B_1") (pintype "passive"))
      (node (ref "R55") (pin "1") (pinfunction "1_1") (pintype "passive"))
    )
    (net (code "64") (name "V5.0") (class "Default")
      (node (ref "R56") (pin "2") (pinfunction "2_2") (pintype "passive"))
    )
    (net (code "65") (name "VCC") (class "Default")
      (node (ref "R18") (pin "1") (pinfunction "1_1") (pintype "passive"))
      (node (ref "R20") (pin "2") (pinfunction "2_2") (pintype "passive"))
      (node (ref "R36") (pin "1") (pinfunction "1_1") (pintype "passive"))
    )
    (net (code "66") (name "VCC_5V") (class "Default")
      (node (ref "P7") (pin "1") (pinfunction "1_1") (pintype "passive"))
      (node (ref "R17") (pin "2") (pinfunction "2_2") (pintype "passive"))
      (node (ref "R34") (pin "2") (pinfunction "2_2") (pintype "passive"))
    )
    (net (code "67") (name "VCC_Heater") (class "Default")
      (node (ref "D1") (pin "2") (pinfunction "K_2") (pintype "passive"))
      (node (ref "D10") (pin "2") (pinfunction "K_2") (pintype "passive"))
      (node (ref "D2") (pin "2") (pinfunction "K_2") (pintype "passive"))
      (node (ref "D3") (pin "2") (pinfunction "K_2") (pintype "passive"))
      (node (ref "D9") (pin "2") (pinfunction "K_2") (pintype "passive"))
      (node (ref "P10") (pin "1") (pinfunction "1_1") (pintype "passive"))
      (node (ref "P12") (pin "1") (pinfunction "1_1") (pintype "passive"))
      (node (ref "P13") (pin "1") (pinfunction "1_1") (pintype "passive"))
      (node (ref "P14") (pin "1") (pinfunction "1_1") (pintype "passive"))
      (node (ref "P15") (pin "1") (pinfunction "1_1") (pintype "passive"))
      (node (ref "P16") (pin "1") (pinfunction "1_1") (pintype "passive"))
      (node (ref "P4") (pin "1") (pinfunction "1_1") (pintype "passive"))
      (node (ref "P6") (pin "1") (pinfunction "1_1") (pintype "passive"))
      (node (ref "P8") (pin "1") (pinfunction "1_1") (pintype "passive"))
      (node (ref "Q12") (pin "3") (pinfunction "C_3") (pintype "passive"))
      (node (ref "Q13") (pin "3") (pinfunction "C_3") (pintype "passive"))
      (node (ref "Q15") (pin "3") (pinfunction "C_3") (pintype "passive"))
      (node (ref "Q3") (pin "3") (pinfunction "C_3") (pintype "passive"))
      (node (ref "Q8") (pin "3") (pinfunction "C_3") (pintype "passive"))
      (node (ref "Q9") (pin "3") (pinfunction "C_3") (pintype "passive"))
      (node (ref "R38") (pin "2") (pinfunction "2_2") (pintype "passive"))
      (node (ref "R39") (pin "2") (pinfunction "2_2") (pintype "passive"))
      (node (ref "R45") (pin "2") (pinfunction "2_2") (pintype "passive"))
      (node (ref "R46") (pin "2") (pinfunction "2_2") (pintype "passive"))
      (node (ref "R47") (pin "2") (pinfunction "2_2") (pintype "passive"))
      (node (ref "U8") (pin "1") (pinfunction "S_1") (pintype "passive"))
      (node (ref "U8") (pin "3") (pinfunction "S_3") (pintype "passive"))
    )
  )
)
